# M651A.net
KiCad netlist of a schematic drawn in EAGLE
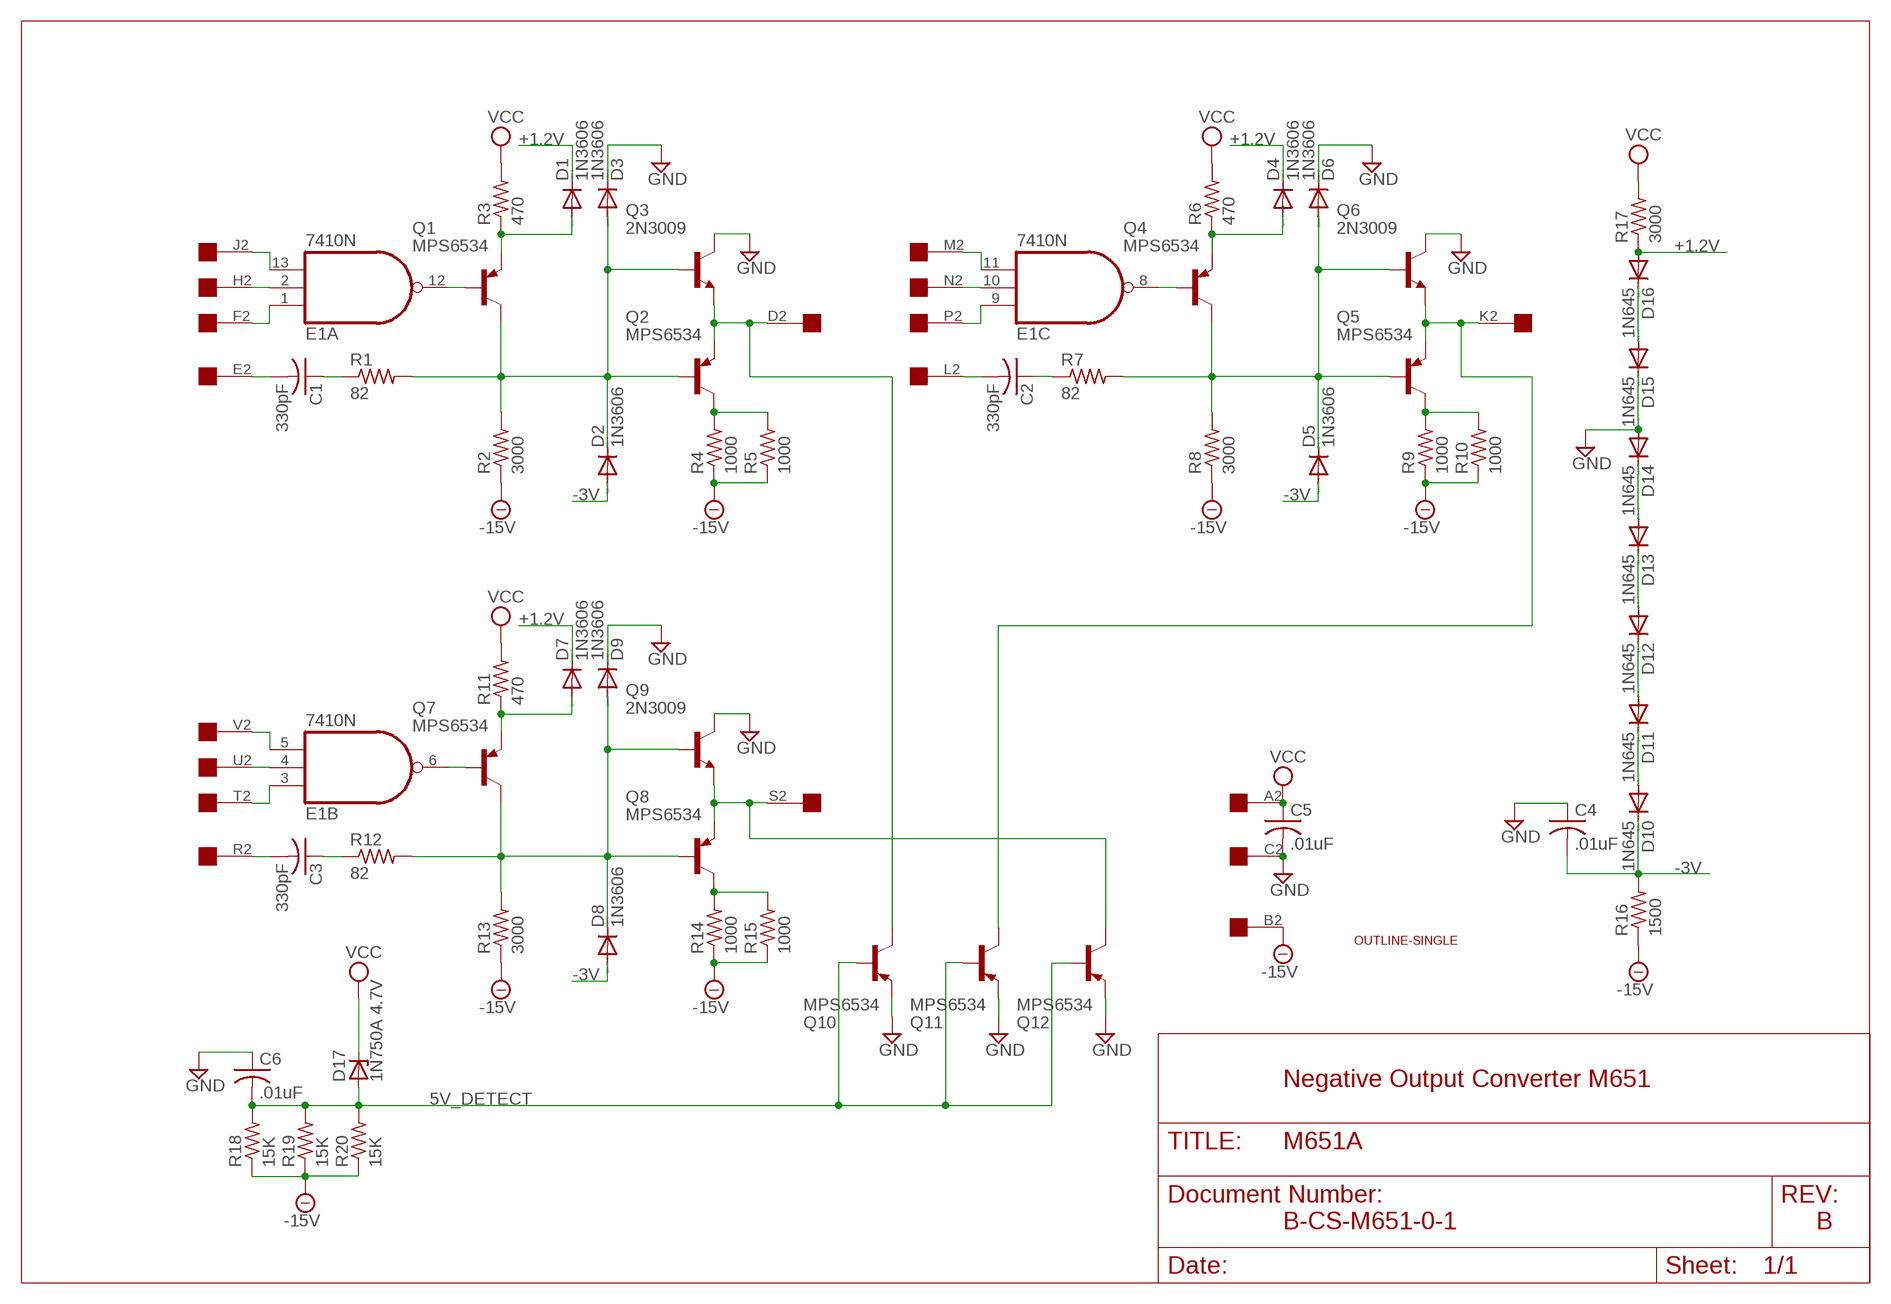
[diagram p0: schematic, sheet 1]

(export (version "E")
  (design (tool "Eeschema 10.0.6"))
  (components
    (comp (ref "C1")
      (value "330pF")
      (footprint "eagle-import:C050-025X075")
      (libsource (lib "eagle-import") (part "C-US050-025X075"))
    )
    (comp (ref "C2")
      (value "330pF")
      (footprint "eagle-import:C050-025X075")
      (libsource (lib "eagle-import") (part "C-US050-025X075"))
    )
    (comp (ref "C3")
      (value "330pF")
      (footprint "eagle-import:C050-025X075")
      (libsource (lib "eagle-import") (part "C-US050-025X075"))
    )
    (comp (ref "C4")
      (value ".01uF")
      (footprint "eagle-import:C050-025X075")
      (libsource (lib "eagle-import") (part "C-US050-025X075"))
    )
    (comp (ref "C5")
      (value ".01uF")
      (footprint "eagle-import:C050-025X075")
      (libsource (lib "eagle-import") (part "C-US050-025X075"))
    )
    (comp (ref "C6")
      (value ".01uF")
      (footprint "eagle-import:C050-025X075")
      (libsource (lib "eagle-import") (part "C-US050-025X075"))
    )
    (comp (ref "D1")
      (value "1N3606")
      (footprint "eagle-import:DO35-10")
      (libsource (lib "eagle-import") (part "1N4148DO35-10"))
    )
    (comp (ref "D2")
      (value "1N3606")
      (footprint "eagle-import:DO35-10")
      (libsource (lib "eagle-import") (part "1N4148DO35-10"))
    )
    (comp (ref "D3")
      (value "1N3606")
      (footprint "eagle-import:DO35-10")
      (libsource (lib "eagle-import") (part "1N4148DO35-10"))
    )
    (comp (ref "D4")
      (value "1N3606")
      (footprint "eagle-import:DO35-10")
      (libsource (lib "eagle-import") (part "1N4148DO35-10"))
    )
    (comp (ref "D5")
      (value "1N3606")
      (footprint "eagle-import:DO35-10")
      (libsource (lib "eagle-import") (part "1N4148DO35-10"))
    )
    (comp (ref "D6")
      (value "1N3606")
      (footprint "eagle-import:DO35-10")
      (libsource (lib "eagle-import") (part "1N4148DO35-10"))
    )
    (comp (ref "D7")
      (value "1N3606")
      (footprint "eagle-import:DO35-10")
      (libsource (lib "eagle-import") (part "1N4148DO35-10"))
    )
    (comp (ref "D8")
      (value "1N3606")
      (footprint "eagle-import:DO35-10")
      (libsource (lib "eagle-import") (part "1N4148DO35-10"))
    )
    (comp (ref "D9")
      (value "1N3606")
      (footprint "eagle-import:DO35-10")
      (libsource (lib "eagle-import") (part "1N4148DO35-10"))
    )
    (comp (ref "D10")
      (value "1N645")
      (footprint "eagle-import:DO35-10")
      (libsource (lib "eagle-import") (part "1N4148DO35-10"))
    )
    (comp (ref "D11")
      (value "1N645")
      (footprint "eagle-import:DO35-10")
      (libsource (lib "eagle-import") (part "1N4148DO35-10"))
    )
    (comp (ref "D12")
      (value "1N645")
      (footprint "eagle-import:DO35-10")
      (libsource (lib "eagle-import") (part "1N4148DO35-10"))
    )
    (comp (ref "D13")
      (value "1N645")
      (footprint "eagle-import:DO35-10")
      (libsource (lib "eagle-import") (part "1N4148DO35-10"))
    )
    (comp (ref "D14")
      (value "1N645")
      (footprint "eagle-import:DO35-10")
      (libsource (lib "eagle-import") (part "1N4148DO35-10"))
    )
    (comp (ref "D15")
      (value "1N645")
      (footprint "eagle-import:DO35-10")
      (libsource (lib "eagle-import") (part "1N4148DO35-10"))
    )
    (comp (ref "D16")
      (value "1N645")
      (footprint "eagle-import:DO35-10")
      (libsource (lib "eagle-import") (part "1N4148DO35-10"))
    )
    (comp (ref "D17")
      (value "1N750A 4.7V")
      (footprint "eagle-import:DO35Z10")
      (libsource (lib "eagle-import") (part "ZENER-DIODEDO35Z10"))
    )
    (comp (ref "E1")
      (value "7410N")
      (footprint "eagle-import:DIL14")
      (libsource (lib "eagle-import") (part "7410N"))
    )
    (comp (ref "Q1")
      (value "MPS6534")
      (footprint "eagle-import:TO39")
      (libsource (lib "eagle-import") (part "2N5415"))
    )
    (comp (ref "Q2")
      (value "MPS6534")
      (footprint "eagle-import:TO39")
      (libsource (lib "eagle-import") (part "2N5415"))
    )
    (comp (ref "Q3")
      (value "2N3009")
      (footprint "eagle-import:TO5")
      (libsource (lib "eagle-import") (part "2N2219"))
    )
    (comp (ref "Q4")
      (value "MPS6534")
      (footprint "eagle-import:TO39")
      (libsource (lib "eagle-import") (part "2N5415"))
    )
    (comp (ref "Q5")
      (value "MPS6534")
      (footprint "eagle-import:TO39")
      (libsource (lib "eagle-import") (part "2N5415"))
    )
    (comp (ref "Q6")
      (value "2N3009")
      (footprint "eagle-import:TO5")
      (libsource (lib "eagle-import") (part "2N2219"))
    )
    (comp (ref "Q7")
      (value "MPS6534")
      (footprint "eagle-import:TO39")
      (libsource (lib "eagle-import") (part "2N5415"))
    )
    (comp (ref "Q8")
      (value "MPS6534")
      (footprint "eagle-import:TO39")
      (libsource (lib "eagle-import") (part "2N5415"))
    )
    (comp (ref "Q9")
      (value "2N3009")
      (footprint "eagle-import:TO5")
      (libsource (lib "eagle-import") (part "2N2219"))
    )
    (comp (ref "Q10")
      (value "MPS6534")
      (footprint "eagle-import:TO39")
      (libsource (lib "eagle-import") (part "2N5415"))
    )
    (comp (ref "Q11")
      (value "MPS6534")
      (footprint "eagle-import:TO39")
      (libsource (lib "eagle-import") (part "2N5415"))
    )
    (comp (ref "Q12")
      (value "MPS6534")
      (footprint "eagle-import:TO39")
      (libsource (lib "eagle-import") (part "2N5415"))
    )
    (comp (ref "R1")
      (value "82")
      (footprint "eagle-import:0207_10")
      (libsource (lib "eagle-import") (part "R-US_0207/10"))
    )
    (comp (ref "R2")
      (value "3000")
      (footprint "eagle-import:0207_10")
      (libsource (lib "eagle-import") (part "R-US_0207/10"))
    )
    (comp (ref "R3")
      (value "470")
      (footprint "eagle-import:0207_10")
      (libsource (lib "eagle-import") (part "R-US_0207/10"))
    )
    (comp (ref "R4")
      (value "1000")
      (footprint "eagle-import:0207_10")
      (libsource (lib "eagle-import") (part "R-US_0207/10"))
    )
    (comp (ref "R5")
      (value "1000")
      (footprint "eagle-import:0207_10")
      (libsource (lib "eagle-import") (part "R-US_0207/10"))
    )
    (comp (ref "R6")
      (value "470")
      (footprint "eagle-import:0207_10")
      (libsource (lib "eagle-import") (part "R-US_0207/10"))
    )
    (comp (ref "R7")
      (value "82")
      (footprint "eagle-import:0207_10")
      (libsource (lib "eagle-import") (part "R-US_0207/10"))
    )
    (comp (ref "R8")
      (value "3000")
      (footprint "eagle-import:0207_10")
      (libsource (lib "eagle-import") (part "R-US_0207/10"))
    )
    (comp (ref "R9")
      (value "1000")
      (footprint "eagle-import:0207_10")
      (libsource (lib "eagle-import") (part "R-US_0207/10"))
    )
    (comp (ref "R10")
      (value "1000")
      (footprint "eagle-import:0207_10")
      (libsource (lib "eagle-import") (part "R-US_0207/10"))
    )
    (comp (ref "R11")
      (value "470")
      (footprint "eagle-import:0207_10")
      (libsource (lib "eagle-import") (part "R-US_0207/10"))
    )
    (comp (ref "R12")
      (value "82")
      (footprint "eagle-import:0207_10")
      (libsource (lib "eagle-import") (part "R-US_0207/10"))
    )
    (comp (ref "R13")
      (value "3000")
      (footprint "eagle-import:0207_10")
      (libsource (lib "eagle-import") (part "R-US_0207/10"))
    )
    (comp (ref "R14")
      (value "1000")
      (footprint "eagle-import:0207_10")
      (libsource (lib "eagle-import") (part "R-US_0207/10"))
    )
    (comp (ref "R15")
      (value "1000")
      (footprint "eagle-import:0207_10")
      (libsource (lib "eagle-import") (part "R-US_0207/10"))
    )
    (comp (ref "R16")
      (value "1500")
      (footprint "eagle-import:0207_10")
      (libsource (lib "eagle-import") (part "R-US_0207/10"))
    )
    (comp (ref "R17")
      (value "3000")
      (footprint "eagle-import:0207_10")
      (libsource (lib "eagle-import") (part "R-US_0207/10"))
    )
    (comp (ref "R18")
      (value "15K")
      (footprint "eagle-import:0207_10")
      (libsource (lib "eagle-import") (part "R-US_0207/10"))
    )
    (comp (ref "R19")
      (value "15K")
      (footprint "eagle-import:0207_10")
      (libsource (lib "eagle-import") (part "R-US_0207/10"))
    )
    (comp (ref "R20")
      (value "15K")
      (footprint "eagle-import:0207_10")
      (libsource (lib "eagle-import") (part "R-US_0207/10"))
    )
    (comp (ref "U$1")
      (value "OUTLINE-SINGLE")
      (footprint "eagle-import:SINGLE")
      (libsource (lib "eagle-import") (part "OUTLINE-SINGLE"))
    )
    (comp (ref "U$3")
      (value "EDGE-1")
      (footprint "eagle-import:EDGE-CON1")
      (libsource (lib "eagle-import") (part "EDGE-1"))
    )
  )
  (nets
    (net (code "1") (name "-15V") (class "Default")
      (node (ref "R10") (pin "1") (pinfunction "1_1") (pintype "passive"))
      (node (ref "R13") (pin "1") (pinfunction "1_1") (pintype "passive"))
      (node (ref "R14") (pin "1") (pinfunction "1_1") (pintype "passive"))
      (node (ref "R15") (pin "1") (pinfunction "1_1") (pintype "passive"))
      (node (ref "R16") (pin "1") (pinfunction "1_1") (pintype "passive"))
      (node (ref "R18") (pin "1") (pinfunction "1_1") (pintype "passive"))
      (node (ref "R19") (pin "1") (pinfunction "1_1") (pintype "passive"))
      (node (ref "R2") (pin "1") (pinfunction "1_1") (pintype "passive"))
      (node (ref "R20") (pin "1") (pinfunction "1_1") (pintype "passive"))
      (node (ref "R4") (pin "1") (pinfunction "1_1") (pintype "passive"))
      (node (ref "R5") (pin "1") (pinfunction "1_1") (pintype "passive"))
      (node (ref "R8") (pin "1") (pinfunction "1_1") (pintype "passive"))
      (node (ref "R9") (pin "1") (pinfunction "1_1") (pintype "passive"))
      (node (ref "U$3") (pin "B2") (pinfunction "1_B2") (pintype "bidirectional"))
    )
    (net (code "2") (name "/+1.2V") (class "Default")
      (node (ref "D1") (pin "C") (pinfunction "C_C") (pintype "passive"))
      (node (ref "D16") (pin "A") (pinfunction "A_A") (pintype "passive"))
      (node (ref "D4") (pin "C") (pinfunction "C_C") (pintype "passive"))
      (node (ref "D7") (pin "C") (pinfunction "C_C") (pintype "passive"))
      (node (ref "R17") (pin "1") (pinfunction "1_1") (pintype "passive"))
    )
    (net (code "3") (name "/-3V") (class "Default")
      (node (ref "C4") (pin "2") (pinfunction "2_2") (pintype "passive"))
      (node (ref "D10") (pin "C") (pinfunction "C_C") (pintype "passive"))
      (node (ref "D2") (pin "A") (pinfunction "A_A") (pintype "passive"))
      (node (ref "D5") (pin "A") (pinfunction "A_A") (pintype "passive"))
      (node (ref "D8") (pin "A") (pinfunction "A_A") (pintype "passive"))
      (node (ref "R16") (pin "2") (pinfunction "2_2") (pintype "passive"))
    )
    (net (code "4") (name "/5V_DETECT") (class "Default")
      (node (ref "C6") (pin "2") (pinfunction "2_2") (pintype "passive"))
      (node (ref "D17") (pin "A") (pinfunction "A_A") (pintype "passive"))
      (node (ref "Q10") (pin "2") (pinfunction "B_2") (pintype "passive"))
      (node (ref "Q11") (pin "2") (pinfunction "B_2") (pintype "passive"))
      (node (ref "Q12") (pin "2") (pinfunction "B_2") (pintype "passive"))
      (node (ref "R18") (pin "2") (pinfunction "2_2") (pintype "passive"))
      (node (ref "R19") (pin "2") (pinfunction "2_2") (pintype "passive"))
      (node (ref "R20") (pin "2") (pinfunction "2_2") (pintype "passive"))
    )
    (net (code "5") (name "GND") (class "Default")
      (node (ref "C4") (pin "1") (pinfunction "1_1") (pintype "passive"))
      (node (ref "C5") (pin "2") (pinfunction "2_2") (pintype "passive"))
      (node (ref "C6") (pin "1") (pinfunction "1_1") (pintype "passive"))
      (node (ref "D14") (pin "A") (pinfunction "A_A") (pintype "passive"))
      (node (ref "D15") (pin "C") (pinfunction "C_C") (pintype "passive"))
      (node (ref "D3") (pin "C") (pinfunction "C_C") (pintype "passive"))
      (node (ref "D6") (pin "C") (pinfunction "C_C") (pintype "passive"))
      (node (ref "D9") (pin "C") (pinfunction "C_C") (pintype "passive"))
      (node (ref "Q10") (pin "1") (pinfunction "E_1") (pintype "passive"))
      (node (ref "Q11") (pin "1") (pinfunction "E_1") (pintype "passive"))
      (node (ref "Q12") (pin "1") (pinfunction "E_1") (pintype "passive"))
      (node (ref "Q3") (pin "3") (pinfunction "C_3") (pintype "passive"))
      (node (ref "Q6") (pin "3") (pinfunction "C_3") (pintype "passive"))
      (node (ref "Q9") (pin "3") (pinfunction "C_3") (pintype "passive"))
      (node (ref "U$3") (pin "C2") (pinfunction "1_C2") (pintype "bidirectional"))
    )
    (net (code "6") (name "Net-(C1-Pad1)") (class "Default")
      (node (ref "C1") (pin "1") (pinfunction "1_1") (pintype "passive"))
      (node (ref "R1") (pin "1") (pinfunction "1_1") (pintype "passive"))
    )
    (net (code "7") (name "Net-(C2-Pad1)") (class "Default")
      (node (ref "C2") (pin "1") (pinfunction "1_1") (pintype "passive"))
      (node (ref "R7") (pin "1") (pinfunction "1_1") (pintype "passive"))
    )
    (net (code "8") (name "Net-(C3-Pad1)") (class "Default")
      (node (ref "C3") (pin "1") (pinfunction "1_1") (pintype "passive"))
      (node (ref "R12") (pin "1") (pinfunction "1_1") (pintype "passive"))
    )
    (net (code "9") (name "Net-(D10-PadA)") (class "Default")
      (node (ref "D10") (pin "A") (pinfunction "A_A") (pintype "passive"))
      (node (ref "D11") (pin "C") (pinfunction "C_C") (pintype "passive"))
    )
    (net (code "10") (name "Net-(D11-PadA)") (class "Default")
      (node (ref "D11") (pin "A") (pinfunction "A_A") (pintype "passive"))
      (node (ref "D12") (pin "C") (pinfunction "C_C") (pintype "passive"))
    )
    (net (code "11") (name "Net-(D12-PadA)") (class "Default")
      (node (ref "D12") (pin "A") (pinfunction "A_A") (pintype "passive"))
      (node (ref "D13") (pin "C") (pinfunction "C_C") (pintype "passive"))
    )
    (net (code "12") (name "Net-(D13-PadA)") (class "Default")
      (node (ref "D13") (pin "A") (pinfunction "A_A") (pintype "passive"))
      (node (ref "D14") (pin "C") (pinfunction "C_C") (pintype "passive"))
    )
    (net (code "13") (name "Net-(D15-PadA)") (class "Default")
      (node (ref "D15") (pin "A") (pinfunction "A_A") (pintype "passive"))
      (node (ref "D16") (pin "C") (pinfunction "C_C") (pintype "passive"))
    )
    (net (code "14") (name "Net-(E1A-I0)") (class "Default")
      (node (ref "E1") (pin "1") (pinfunction "I0_1") (pintype "input"))
      (node (ref "U$3") (pin "F2") (pinfunction "1_F2") (pintype "bidirectional"))
    )
    (net (code "15") (name "Net-(E1A-I1)") (class "Default")
      (node (ref "E1") (pin "2") (pinfunction "I1_2") (pintype "input"))
      (node (ref "U$3") (pin "H2") (pinfunction "1_H2") (pintype "bidirectional"))
    )
    (net (code "16") (name "Net-(E1A-I2)") (class "Default")
      (node (ref "E1") (pin "13") (pinfunction "I2_13") (pintype "input"))
      (node (ref "U$3") (pin "J2") (pinfunction "1_J2") (pintype "bidirectional"))
    )
    (net (code "17") (name "Net-(E1A-O)") (class "Default")
      (node (ref "E1") (pin "12") (pinfunction "O_12") (pintype "output"))
      (node (ref "Q1") (pin "2") (pinfunction "B_2") (pintype "passive"))
    )
    (net (code "18") (name "Net-(E1B-I0)") (class "Default")
      (node (ref "E1") (pin "3") (pinfunction "I0_3") (pintype "input"))
      (node (ref "U$3") (pin "T2") (pinfunction "1_T2") (pintype "bidirectional"))
    )
    (net (code "19") (name "Net-(E1B-I1)") (class "Default")
      (node (ref "E1") (pin "4") (pinfunction "I1_4") (pintype "input"))
      (node (ref "U$3") (pin "U2") (pinfunction "1_U2") (pintype "bidirectional"))
    )
    (net (code "20") (name "Net-(E1B-I2)") (class "Default")
      (node (ref "E1") (pin "5") (pinfunction "I2_5") (pintype "input"))
      (node (ref "U$3") (pin "V2") (pinfunction "1_V2") (pintype "bidirectional"))
    )
    (net (code "21") (name "Net-(E1B-O)") (class "Default")
      (node (ref "E1") (pin "6") (pinfunction "O_6") (pintype "output"))
      (node (ref "Q7") (pin "2") (pinfunction "B_2") (pintype "passive"))
    )
    (net (code "22") (name "Net-(E1C-I0)") (class "Default")
      (node (ref "E1") (pin "9") (pinfunction "I0_9") (pintype "input"))
      (node (ref "U$3") (pin "P2") (pinfunction "1_P2") (pintype "bidirectional"))
    )
    (net (code "23") (name "Net-(E1C-I1)") (class "Default")
      (node (ref "E1") (pin "10") (pinfunction "I1_10") (pintype "input"))
      (node (ref "U$3") (pin "N2") (pinfunction "1_N2") (pintype "bidirectional"))
    )
    (net (code "24") (name "Net-(E1C-I2)") (class "Default")
      (node (ref "E1") (pin "11") (pinfunction "I2_11") (pintype "input"))
      (node (ref "U$3") (pin "M2") (pinfunction "1_M2") (pintype "bidirectional"))
    )
    (net (code "25") (name "Net-(E1C-O)") (class "Default")
      (node (ref "E1") (pin "8") (pinfunction "O_8") (pintype "output"))
      (node (ref "Q4") (pin "2") (pinfunction "B_2") (pintype "passive"))
    )
    (net (code "26") (name "Net-(Q1-C)") (class "Default")
      (node (ref "D2") (pin "C") (pinfunction "C_C") (pintype "passive"))
      (node (ref "D3") (pin "A") (pinfunction "A_A") (pintype "passive"))
      (node (ref "Q1") (pin "3") (pinfunction "C_3") (pintype "passive"))
      (node (ref "Q2") (pin "2") (pinfunction "B_2") (pintype "passive"))
      (node (ref "Q3") (pin "2") (pinfunction "B_2") (pintype "passive"))
      (node (ref "R1") (pin "2") (pinfunction "2_2") (pintype "passive"))
      (node (ref "R2") (pin "2") (pinfunction "2_2") (pintype "passive"))
    )
    (net (code "27") (name "Net-(Q1-E)") (class "Default")
      (node (ref "D1") (pin "A") (pinfunction "A_A") (pintype "passive"))
      (node (ref "Q1") (pin "1") (pinfunction "E_1") (pintype "passive"))
      (node (ref "R3") (pin "1") (pinfunction "1_1") (pintype "passive"))
    )
    (net (code "28") (name "Net-(Q2-C)") (class "Default")
      (node (ref "Q2") (pin "3") (pinfunction "C_3") (pintype "passive"))
      (node (ref "R4") (pin "2") (pinfunction "2_2") (pintype "passive"))
      (node (ref "R5") (pin "2") (pinfunction "2_2") (pintype "passive"))
    )
    (net (code "29") (name "Net-(Q4-C)") (class "Default")
      (node (ref "D5") (pin "C") (pinfunction "C_C") (pintype "passive"))
      (node (ref "D6") (pin "A") (pinfunction "A_A") (pintype "passive"))
      (node (ref "Q4") (pin "3") (pinfunction "C_3") (pintype "passive"))
      (node (ref "Q5") (pin "2") (pinfunction "B_2") (pintype "passive"))
      (node (ref "Q6") (pin "2") (pinfunction "B_2") (pintype "passive"))
      (node (ref "R7") (pin "2") (pinfunction "2_2") (pintype "passive"))
      (node (ref "R8") (pin "2") (pinfunction "2_2") (pintype "passive"))
    )
    (net (code "30") (name "Net-(Q4-E)") (class "Default")
      (node (ref "D4") (pin "A") (pinfunction "A_A") (pintype "passive"))
      (node (ref "Q4") (pin "1") (pinfunction "E_1") (pintype "passive"))
      (node (ref "R6") (pin "1") (pinfunction "1_1") (pintype "passive"))
    )
    (net (code "31") (name "Net-(Q5-C)") (class "Default")
      (node (ref "Q5") (pin "3") (pinfunction "C_3") (pintype "passive"))
      (node (ref "R10") (pin "2") (pinfunction "2_2") (pintype "passive"))
      (node (ref "R9") (pin "2") (pinfunction "2_2") (pintype "passive"))
    )
    (net (code "32") (name "Net-(Q7-C)") (class "Default")
      (node (ref "D8") (pin "C") (pinfunction "C_C") (pintype "passive"))
      (node (ref "D9") (pin "A") (pinfunction "A_A") (pintype "passive"))
      (node (ref "Q7") (pin "3") (pinfunction "C_3") (pintype "passive"))
      (node (ref "Q8") (pin "2") (pinfunction "B_2") (pintype "passive"))
      (node (ref "Q9") (pin "2") (pinfunction "B_2") (pintype "passive"))
      (node (ref "R12") (pin "2") (pinfunction "2_2") (pintype "passive"))
      (node (ref "R13") (pin "2") (pinfunction "2_2") (pintype "passive"))
    )
    (net (code "33") (name "Net-(Q7-E)") (class "Default")
      (node (ref "D7") (pin "A") (pinfunction "A_A") (pintype "passive"))
      (node (ref "Q7") (pin "1") (pinfunction "E_1") (pintype "passive"))
      (node (ref "R11") (pin "1") (pinfunction "1_1") (pintype "passive"))
    )
    (net (code "34") (name "Net-(Q8-C)") (class "Default")
      (node (ref "Q8") (pin "3") (pinfunction "C_3") (pintype "passive"))
      (node (ref "R14") (pin "2") (pinfunction "2_2") (pintype "passive"))
      (node (ref "R15") (pin "2") (pinfunction "2_2") (pintype "passive"))
    )
    (net (code "35") (name "Net-(Q10-C)") (class "Default")
      (node (ref "Q10") (pin "3") (pinfunction "C_3") (pintype "passive"))
      (node (ref "Q2") (pin "1") (pinfunction "E_1") (pintype "passive"))
      (node (ref "Q3") (pin "1") (pinfunction "E_1") (pintype "passive"))
      (node (ref "U$3") (pin "D2") (pinfunction "1_D2") (pintype "bidirectional"))
    )
    (net (code "36") (name "Net-(Q11-C)") (class "Default")
      (node (ref "Q11") (pin "3") (pinfunction "C_3") (pintype "passive"))
      (node (ref "Q5") (pin "1") (pinfunction "E_1") (pintype "passive"))
      (node (ref "Q6") (pin "1") (pinfunction "E_1") (pintype "passive"))
      (node (ref "U$3") (pin "K2") (pinfunction "1_K2") (pintype "bidirectional"))
    )
    (net (code "37") (name "Net-(Q12-C)") (class "Default")
      (node (ref "Q12") (pin "3") (pinfunction "C_3") (pintype "passive"))
      (node (ref "Q8") (pin "1") (pinfunction "E_1") (pintype "passive"))
      (node (ref "Q9") (pin "1") (pinfunction "E_1") (pintype "passive"))
      (node (ref "U$3") (pin "S2") (pinfunction "1_S2") (pintype "bidirectional"))
    )
    (net (code "38") (name "Net-(U$3E-1)") (class "Default")
      (node (ref "C1") (pin "2") (pinfunction "2_2") (pintype "passive"))
      (node (ref "U$3") (pin "E2") (pinfunction "1_E2") (pintype "bidirectional"))
    )
    (net (code "39") (name "Net-(U$3J-1)") (class "Default")
      (node (ref "C2") (pin "2") (pinfunction "2_2") (pintype "passive"))
      (node (ref "U$3") (pin "L2") (pinfunction "1_L2") (pintype "bidirectional"))
    )
    (net (code "40") (name "Net-(U$3N-1)") (class "Default")
      (node (ref "C3") (pin "2") (pinfunction "2_2") (pintype "passive"))
      (node (ref "U$3") (pin "R2") (pinfunction "1_R2") (pintype "bidirectional"))
    )
    (net (code "41") (name "VCC") (class "Default")
      (node (ref "C5") (pin "1") (pinfunction "1_1") (pintype "passive"))
      (node (ref "D17") (pin "C") (pinfunction "C_C") (pintype "passive"))
      (node (ref "R11") (pin "2") (pinfunction "2_2") (pintype "passive"))
      (node (ref "R17") (pin "2") (pinfunction "2_2") (pintype "passive"))
      (node (ref "R3") (pin "2") (pinfunction "2_2") (pintype "passive"))
      (node (ref "R6") (pin "2") (pinfunction "2_2") (pintype "passive"))
      (node (ref "U$3") (pin "A2") (pinfunction "1_A2") (pintype "bidirectional"))
    )
  )
)
